# BLUETOOTH.net
KiCad netlist of a schematic drawn in Altium Designer
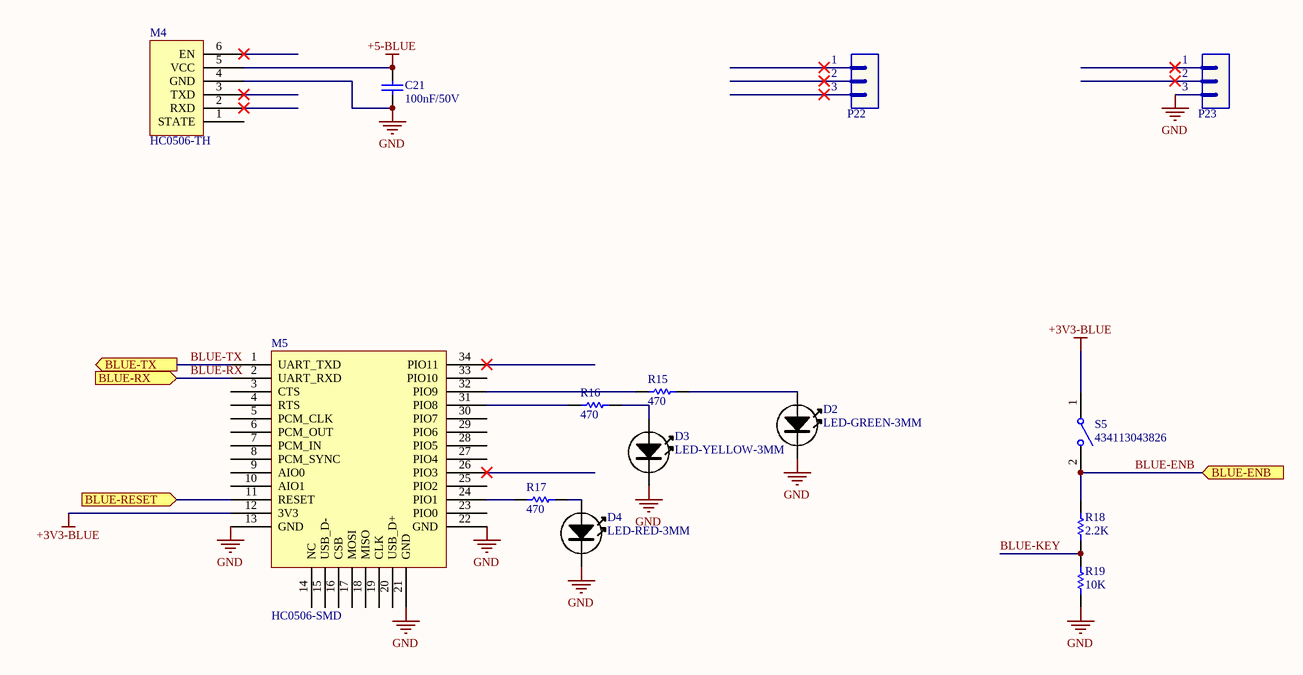
[diagram p0: BLUETOOTH.SchDoc]

(export (version "E")
  (design (tool "Eeschema 10.0.6"))
  (components
    (comp (ref "C21")
      (value "100nF/50V")
      (footprint "CAP-SM-0805")
      (description "CAP CER 0.1UF 50V Y5V 0805")
      (fields
        (field (name "MANUFACTURER") "Samsung Electro-Mechanics")
        (field (name "MANUFACTURER PART NUMBER") "CL21F104ZBCNNNC")
      )
      (libsource (lib "Capacitor") (part "Cap-100nF-50V-0805"))
    )
    (comp (ref "D2")
      (value "LED-GREEN-3MM")
      (footprint "LED-3MM-GREEN")
      (libsource (lib "vh_altium_library") (part "LED-GREEN-3MM"))
    )
    (comp (ref "D3")
      (value "LED-YELLOW-3MM")
      (footprint "LED-3MM-YELLOW")
      (libsource (lib "vh_altium_library") (part "LED-YELLOW-3MM"))
    )
    (comp (ref "D4")
      (value "LED-RED-3MM")
      (footprint "LED-3MM-RED")
      (libsource (lib "vh_altium_library") (part "LED-RED-3MM"))
    )
    (comp (ref "M4") (value "HC0506-TH") (libsource (lib "MyLibrary1") (part "HC0506-TH")))
    (comp (ref "M5") (value "HC0506-SMD") (libsource (lib "MyLibrary1") (part "HC0506-SMD")))
    (comp (ref "P22")
      (value "Header 3")
      (footprint "JP3")
      (description "Header, 3-Pin")
      (fields (field (name "PUBLISHER") "Altium Limited"))
      (libsource (lib "Header-connector") (part "Header 3"))
    )
    (comp (ref "P23")
      (value "Header 3")
      (footprint "JP3")
      (description "Header, 3-Pin")
      (fields (field (name "PUBLISHER") "Altium Limited"))
      (libsource (lib "Header-connector") (part "Header 3"))
    )
    (comp (ref "R15")
      (value "470")
      (footprint "Resistor:RES-SM-0805")
      (description "RES 470 OHM JUMPER 0805")
      (fields
        (field (name "MANUFACTURER") "YAG6006CT-ND")
        (field (name "MANUFACTURER PART NUMBER") "PE0805FRF7W0R047L")
      )
      (libsource (lib "Resistor") (part "Res-470-0805"))
    )
    (comp (ref "R16")
      (value "470")
      (footprint "Resistor:RES-SM-0805")
      (description "RES 470 OHM JUMPER 0805")
      (fields
        (field (name "MANUFACTURER") "YAG6006CT-ND")
        (field (name "MANUFACTURER PART NUMBER") "PE0805FRF7W0R047L")
      )
      (libsource (lib "Resistor") (part "Res-470-0805"))
    )
    (comp (ref "R17")
      (value "470")
      (footprint "Resistor:RES-SM-0805")
      (description "RES 470 OHM JUMPER 0805")
      (fields
        (field (name "MANUFACTURER") "YAG6006CT-ND")
        (field (name "MANUFACTURER PART NUMBER") "PE0805FRF7W0R047L")
      )
      (libsource (lib "Resistor") (part "Res-470-0805"))
    )
    (comp (ref "R18")
      (value "2.2K")
      (footprint "Resistor:RES-SM-0805")
      (description "RES SMD 2.2K OHM 1% 1/8W 0805")
      (fields
        (field (name "MANUFACTURER") "TE Connectivity Passive Product")
        (field (name "MANUFACTURER PART NUMBER") "CRG0805F2K2")
      )
      (libsource (lib "Resistor") (part "Res-2.2K-0805"))
    )
    (comp (ref "R19")
      (value "10K")
      (footprint "Resistor:RES-SM-0805")
      (description "RES 10K OHM 1% 1/4W 0805")
      (fields
        (field (name "MANUFACTURER") "Stackpole Electronics Inc")
        (field (name "MANUFACTURER PART NUMBER") "RNCP0805FTD10K0")
      )
      (libsource (lib "Resistor") (part "Res-10k-0805"))
    )
    (comp (ref "S5")
      (value "434113043826")
      (footprint "434113043826")
      (description "WS-TASV J-Bend SMT Tact Switch 6x3.5mm, height 4.3mm, 260gf")
      (fields (field (name "PUBLISHER") "Wurth Elektronik"))
      (libsource (lib "434113043826_Altium_WS-TASV_rev20a") (part "434113043826"))
    )
  )
  (nets
    (net (code "1") (name "+3V3-BLUE") (class "Default")
      (node (ref "M5") (pin "12") (pinfunction "3V3_12") (pintype "passive"))
      (node (ref "S5") (pin "1") (pinfunction "1_1") (pintype "passive"))
    )
    (net (code "2") (name "+5-BLUE") (class "Default")
      (node (ref "C21") (pin "2") (pinfunction "2_2") (pintype "passive"))
      (node (ref "M4") (pin "5") (pinfunction "VCC_5") (pintype "passive"))
    )
    (net (code "3") (name "/BLUE-ENB") (class "Default")
      (node (ref "R18") (pin "2") (pinfunction "2_2") (pintype "passive"))
      (node (ref "S5") (pin "2") (pinfunction "2_2") (pintype "passive"))
    )
    (net (code "4") (name "/BLUE-KEY") (class "Default")
      (node (ref "R18") (pin "1") (pinfunction "1_1") (pintype "passive"))
      (node (ref "R19") (pin "2") (pinfunction "2_2") (pintype "passive"))
    )
    (net (code "5") (name "/BLUE-RESET") (class "Default")
      (node (ref "M5") (pin "11") (pinfunction "RESET_11") (pintype "passive"))
    )
    (net (code "6") (name "/BLUE-RX") (class "Default")
      (node (ref "M5") (pin "2") (pinfunction "UART_RXD_2") (pintype "passive"))
    )
    (net (code "7") (name "/BLUE-TX") (class "Default")
      (node (ref "M5") (pin "1") (pinfunction "UART_TXD_1") (pintype "passive"))
    )
    (net (code "8") (name "GND") (class "Default")
      (node (ref "C21") (pin "1") (pinfunction "1_1") (pintype "passive"))
      (node (ref "D2") (pin "K") (pintype "passive"))
      (node (ref "D3") (pin "K") (pintype "passive"))
      (node (ref "D4") (pin "K") (pintype "passive"))
      (node (ref "M4") (pin "4") (pinfunction "GND_4") (pintype "passive"))
      (node (ref "M5") (pin "13") (pinfunction "GND_13") (pintype "passive"))
      (node (ref "M5") (pin "21") (pinfunction "GND_21") (pintype "passive"))
      (node (ref "M5") (pin "22") (pinfunction "GND_22") (pintype "passive"))
      (node (ref "P23") (pin "3") (pinfunction "3_3") (pintype "passive"))
      (node (ref "R19") (pin "1") (pinfunction "1_1") (pintype "passive"))
    )
    (net (code "9") (name "Net-(D2-PadA)") (class "Default")
      (node (ref "D2") (pin "A") (pintype "passive"))
      (node (ref "R15") (pin "2") (pinfunction "2_2") (pintype "passive"))
    )
    (net (code "10") (name "Net-(D3-PadA)") (class "Default")
      (node (ref "D3") (pin "A") (pintype "passive"))
      (node (ref "R16") (pin "2") (pinfunction "2_2") (pintype "passive"))
    )
    (net (code "11") (name "Net-(D4-PadA)") (class "Default")
      (node (ref "D4") (pin "A") (pintype "passive"))
      (node (ref "R17") (pin "2") (pinfunction "2_2") (pintype "passive"))
    )
    (net (code "12") (name "Net-(M5-PIO1)") (class "Default")
      (node (ref "M5") (pin "24") (pinfunction "PIO1_24") (pintype "passive"))
      (node (ref "R17") (pin "1") (pinfunction "1_1") (pintype "passive"))
    )
    (net (code "13") (name "Net-(M5-PIO8)") (class "Default")
      (node (ref "M5") (pin "31") (pinfunction "PIO8_31") (pintype "passive"))
      (node (ref "R16") (pin "1") (pinfunction "1_1") (pintype "passive"))
    )
    (net (code "14") (name "Net-(M5-PIO9)") (class "Default")
      (node (ref "M5") (pin "32") (pinfunction "PIO9_32") (pintype "passive"))
      (node (ref "R15") (pin "1") (pinfunction "1_1") (pintype "passive"))
    )
    (net (code "15") (name "unconnected-(M4-EN-Pad6)") (class "Default")
      (node (ref "M4") (pin "6") (pinfunction "EN_6") (pintype "passive+no_connect"))
    )
    (net (code "16") (name "unconnected-(M4-RXD-Pad2)") (class "Default")
      (node (ref "M4") (pin "2") (pinfunction "RXD_2") (pintype "passive+no_connect"))
    )
    (net (code "17") (name "unconnected-(M4-STATE-Pad1)") (class "Default")
      (node (ref "M4") (pin "1") (pinfunction "STATE_1") (pintype "passive"))
    )
    (net (code "18") (name "unconnected-(M4-TXD-Pad3)") (class "Default")
      (node (ref "M4") (pin "3") (pinfunction "TXD_3") (pintype "passive+no_connect"))
    )
    (net (code "19") (name "unconnected-(M5-AIO0-Pad9)") (class "Default")
      (node (ref "M5") (pin "9") (pinfunction "AIO0_9") (pintype "passive"))
    )
    (net (code "20") (name "unconnected-(M5-AIO1-Pad10)") (class "Default")
      (node (ref "M5") (pin "10") (pinfunction "AIO1_10") (pintype "passive"))
    )
    (net (code "21") (name "unconnected-(M5-CLK-Pad19)") (class "Default")
      (node (ref "M5") (pin "19") (pinfunction "CLK_19") (pintype "passive"))
    )
    (net (code "22") (name "unconnected-(M5-CSB-Pad16)") (class "Default")
      (node (ref "M5") (pin "16") (pinfunction "CSB_16") (pintype "passive"))
    )
    (net (code "23") (name "unconnected-(M5-CTS-Pad3)") (class "Default")
      (node (ref "M5") (pin "3") (pinfunction "CTS_3") (pintype "passive"))
    )
    (net (code "24") (name "unconnected-(M5-MISO-Pad18)") (class "Default")
      (node (ref "M5") (pin "18") (pinfunction "MISO_18") (pintype "passive"))
    )
    (net (code "25") (name "unconnected-(M5-MOSI-Pad17)") (class "Default")
      (node (ref "M5") (pin "17") (pinfunction "MOSI_17") (pintype "passive"))
    )
    (net (code "26") (name "unconnected-(M5-NC-Pad14)") (class "Default")
      (node (ref "M5") (pin "14") (pinfunction "NC_14") (pintype "passive"))
    )
    (net (code "27") (name "unconnected-(M5-PCM_CLK-Pad5)") (class "Default")
      (node (ref "M5") (pin "5") (pinfunction "PCM_CLK_5") (pintype "passive"))
    )
    (net (code "28") (name "unconnected-(M5-PCM_IN-Pad7)") (class "Default")
      (node (ref "M5") (pin "7") (pinfunction "PCM_IN_7") (pintype "passive"))
    )
    (net (code "29") (name "unconnected-(M5-PCM_OUT-Pad6)") (class "Default")
      (node (ref "M5") (pin "6") (pinfunction "PCM_OUT_6") (pintype "passive"))
    )
    (net (code "30") (name "unconnected-(M5-PCM_SYNC-Pad8)") (class "Default")
      (node (ref "M5") (pin "8") (pinfunction "PCM_SYNC_8") (pintype "passive"))
    )
    (net (code "31") (name "unconnected-(M5-PIO0-Pad23)") (class "Default")
      (node (ref "M5") (pin "23") (pinfunction "PIO0_23") (pintype "passive"))
    )
    (net (code "32") (name "unconnected-(M5-PIO2-Pad25)") (class "Default")
      (node (ref "M5") (pin "25") (pinfunction "PIO2_25") (pintype "passive"))
    )
    (net (code "33") (name "unconnected-(M5-PIO3-Pad26)") (class "Default")
      (node (ref "M5") (pin "26") (pinfunction "PIO3_26") (pintype "passive+no_connect"))
    )
    (net (code "34") (name "unconnected-(M5-PIO4-Pad27)") (class "Default")
      (node (ref "M5") (pin "27") (pinfunction "PIO4_27") (pintype "passive"))
    )
    (net (code "35") (name "unconnected-(M5-PIO5-Pad28)") (class "Default")
      (node (ref "M5") (pin "28") (pinfunction "PIO5_28") (pintype "passive"))
    )
    (net (code "36") (name "unconnected-(M5-PIO6-Pad29)") (class "Default")
      (node (ref "M5") (pin "29") (pinfunction "PIO6_29") (pintype "passive"))
    )
    (net (code "37") (name "unconnected-(M5-PIO7-Pad30)") (class "Default")
      (node (ref "M5") (pin "30") (pinfunction "PIO7_30") (pintype "passive"))
    )
    (net (code "38") (name "unconnected-(M5-PIO10-Pad33)") (class "Default")
      (node (ref "M5") (pin "33") (pinfunction "PIO10_33") (pintype "passive"))
    )
    (net (code "39") (name "unconnected-(M5-PIO11-Pad34)") (class "Default")
      (node (ref "M5") (pin "34") (pinfunction "PIO11_34") (pintype "passive+no_connect"))
    )
    (net (code "40") (name "unconnected-(M5-RTS-Pad4)") (class "Default")
      (node (ref "M5") (pin "4") (pinfunction "RTS_4") (pintype "passive"))
    )
    (net (code "41") (name "unconnected-(M5-USB_D+-Pad20)") (class "Default")
      (node (ref "M5") (pin "20") (pinfunction "USB_D+_20") (pintype "passive"))
    )
    (net (code "42") (name "unconnected-(M5-USB_D--Pad15)") (class "Default")
      (node (ref "M5") (pin "15") (pinfunction "USB_D-_15") (pintype "passive"))
    )
    (net (code "43") (name "unconnected-(P22-Pad1)") (class "Default")
      (node (ref "P22") (pin "1") (pinfunction "1_1") (pintype "passive+no_connect"))
    )
    (net (code "44") (name "unconnected-(P22-Pad2)") (class "Default")
      (node (ref "P22") (pin "2") (pinfunction "2_2") (pintype "passive+no_connect"))
    )
    (net (code "45") (name "unconnected-(P22-Pad3)") (class "Default")
      (node (ref "P22") (pin "3") (pinfunction "3_3") (pintype "passive+no_connect"))
    )
    (net (code "46") (name "unconnected-(P23-Pad1)") (class "Default")
      (node (ref "P23") (pin "1") (pinfunction "1_1") (pintype "passive+no_connect"))
    )
    (net (code "47") (name "unconnected-(P23-Pad2)") (class "Default")
      (node (ref "P23") (pin "2") (pinfunction "2_2") (pintype "passive+no_connect"))
    )
  )
)
